# 04A-005.net
KiCad netlist of a schematic drawn in EAGLE
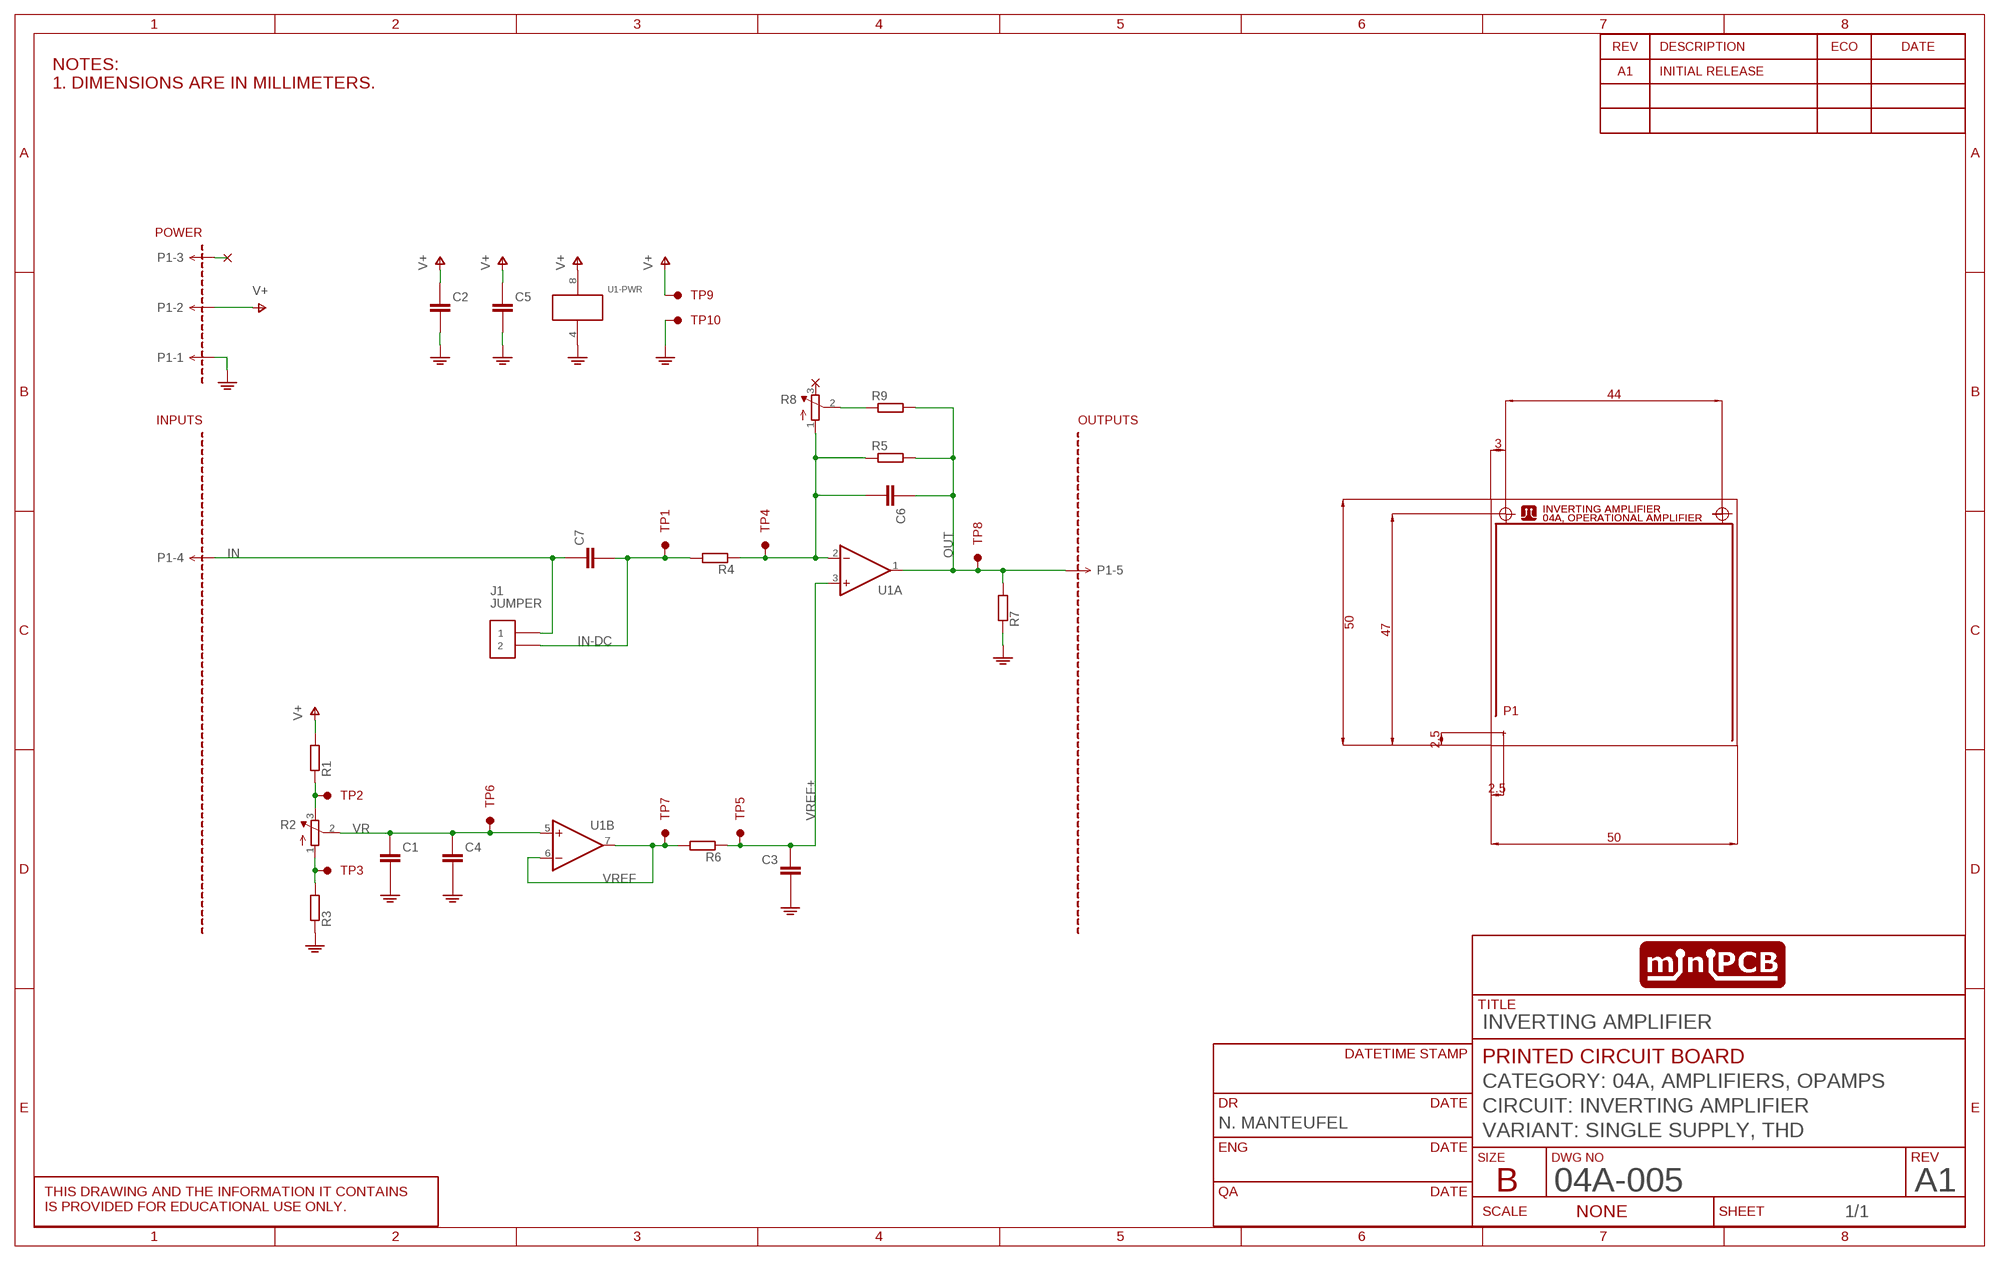
[diagram p0: schematic, sheet 1]

(export (version "E")
  (design (tool "Eeschema 10.0.6"))
  (components
    (comp (ref "C1")
      (value "CAPACITOR_10")
      (footprint "eagle-import:C5MM")
      (libsource (lib "eagle-import") (part "CAPACITOR_10"))
    )
    (comp (ref "C2")
      (value "CAPACITORTHD")
      (footprint "eagle-import:C050-024X044")
      (libsource (lib "eagle-import") (part "CAPACITORTHD"))
    )
    (comp (ref "C3")
      (value "CAPACITORTHD")
      (footprint "eagle-import:C050-024X044")
      (libsource (lib "eagle-import") (part "CAPACITORTHD"))
    )
    (comp (ref "C4")
      (value "CAPACITORTHD")
      (footprint "eagle-import:C050-024X044")
      (libsource (lib "eagle-import") (part "CAPACITORTHD"))
    )
    (comp (ref "C5")
      (value "CAPACITOR_10")
      (footprint "eagle-import:C5MM")
      (libsource (lib "eagle-import") (part "CAPACITOR_10"))
    )
    (comp (ref "C6")
      (value "CAPACITORTHD")
      (footprint "eagle-import:C050-024X044")
      (libsource (lib "eagle-import") (part "CAPACITORTHD"))
    )
    (comp (ref "C7")
      (value "CAPACITORTHD")
      (footprint "eagle-import:C050-024X044")
      (libsource (lib "eagle-import") (part "CAPACITORTHD"))
    )
    (comp (ref "J1")
      (value "JUMPER")
      (footprint "eagle-import:PINS_2")
      (libsource (lib "eagle-import") (part "PINS_2"))
    )
    (comp (ref "P1")
      (value "MINIPCB_5P5P")
      (footprint "eagle-import:PINS_1X5")
      (libsource (lib "eagle-import") (part "MINIPCB_5P5P"))
    )
    (comp (ref "R1")
      (value "RESISTOR10MM")
      (footprint "eagle-import:0207_10")
      (libsource (lib "eagle-import") (part "RESISTOR10MM"))
    )
    (comp (ref "R2")
      (value "TRIMPOT0.100THD")
      (footprint "eagle-import:TRIM_0100")
      (libsource (lib "eagle-import") (part "TRIMPOT0.100THD"))
    )
    (comp (ref "R3")
      (value "RESISTOR10MM")
      (footprint "eagle-import:0207_10")
      (libsource (lib "eagle-import") (part "RESISTOR10MM"))
    )
    (comp (ref "R4")
      (value "RESISTOR10MM")
      (footprint "eagle-import:0207_10")
      (libsource (lib "eagle-import") (part "RESISTOR10MM"))
    )
    (comp (ref "R5")
      (value "RESISTOR10MM")
      (footprint "eagle-import:0207_10")
      (libsource (lib "eagle-import") (part "RESISTOR10MM"))
    )
    (comp (ref "R6")
      (value "RESISTOR10MM")
      (footprint "eagle-import:0207_10")
      (libsource (lib "eagle-import") (part "RESISTOR10MM"))
    )
    (comp (ref "R7")
      (value "RESISTOR10MM")
      (footprint "eagle-import:0207_10")
      (libsource (lib "eagle-import") (part "RESISTOR10MM"))
    )
    (comp (ref "R8")
      (value "TRIMPOT0.100THD")
      (footprint "eagle-import:TRIM_0100")
      (libsource (lib "eagle-import") (part "TRIMPOT0.100THD"))
    )
    (comp (ref "R9")
      (value "RESISTOR10MM")
      (footprint "eagle-import:0207_10")
      (libsource (lib "eagle-import") (part "RESISTOR10MM"))
    )
    (comp (ref "TP1")
      (value "TESTPOINTKE5000-SMTEXT")
      (footprint "eagle-import:PINS_1_TESTPOINT_KE5000_NOTEXT")
      (libsource (lib "eagle-import") (part "TESTPOINTKE5000-SMTEXT"))
    )
    (comp (ref "TP2")
      (value "TESTPOINTKE5000-SMTEXT")
      (footprint "eagle-import:PINS_1_TESTPOINT_KE5000_NOTEXT")
      (libsource (lib "eagle-import") (part "TESTPOINTKE5000-SMTEXT"))
    )
    (comp (ref "TP3")
      (value "TESTPOINTKE5000-SMTEXT")
      (footprint "eagle-import:PINS_1_TESTPOINT_KE5000_NOTEXT")
      (libsource (lib "eagle-import") (part "TESTPOINTKE5000-SMTEXT"))
    )
    (comp (ref "TP4")
      (value "TESTPOINTKE5000-SMTEXT")
      (footprint "eagle-import:PINS_1_TESTPOINT_KE5000_NOTEXT")
      (libsource (lib "eagle-import") (part "TESTPOINTKE5000-SMTEXT"))
    )
    (comp (ref "TP5")
      (value "TESTPOINTKE5000-SMTEXT")
      (footprint "eagle-import:PINS_1_TESTPOINT_KE5000_NOTEXT")
      (libsource (lib "eagle-import") (part "TESTPOINTKE5000-SMTEXT"))
    )
    (comp (ref "TP6")
      (value "TESTPOINTKE5000-SMTEXT")
      (footprint "eagle-import:PINS_1_TESTPOINT_KE5000_NOTEXT")
      (libsource (lib "eagle-import") (part "TESTPOINTKE5000-SMTEXT"))
    )
    (comp (ref "TP7")
      (value "TESTPOINTKE5000-SMTEXT")
      (footprint "eagle-import:PINS_1_TESTPOINT_KE5000_NOTEXT")
      (libsource (lib "eagle-import") (part "TESTPOINTKE5000-SMTEXT"))
    )
    (comp (ref "TP8")
      (value "TESTPOINTKE5000-SMTEXT")
      (footprint "eagle-import:PINS_1_TESTPOINT_KE5000_NOTEXT")
      (libsource (lib "eagle-import") (part "TESTPOINTKE5000-SMTEXT"))
    )
    (comp (ref "TP9")
      (value "TESTPOINTKE5000-SMTEXT")
      (footprint "eagle-import:PINS_1_TESTPOINT_KE5000_NOTEXT")
      (libsource (lib "eagle-import") (part "TESTPOINTKE5000-SMTEXT"))
    )
    (comp (ref "TP10")
      (value "TESTPOINTKE5000-SMTEXT")
      (footprint "eagle-import:PINS_1_TESTPOINT_KE5000_NOTEXT")
      (libsource (lib "eagle-import") (part "TESTPOINTKE5000-SMTEXT"))
    )
    (comp (ref "U$1")
      (value "MINIPCB_50X50")
      (footprint "eagle-import:MINIPCB_0P_50X50MM")
      (fields
        (field (name "TITLE") "TITLE")
        (field (name "CIRCUIT_CATEGORY") "CIRCUIT CATEGORY")
        (field (name "PART_NUMBER") "PART NUMBER")
        (field (name "CIRCUIT_CATEGORY_1") "04A, OPERATIONAL AMPLIFIER")
        (field (name "PART_NUMBER_1") "04A-005")
        (field (name "REVISION") "A1-01")
        (field (name "TITLE_1") "INVERTING AMPLIFIER")
      )
      (libsource (lib "eagle-import") (part "MINIPCB_50X50"))
    )
    (comp (ref "U1")
      (value "OPAMP_DUALTHD")
      (footprint "eagle-import:DIL08")
      (libsource (lib "eagle-import") (part "OPAMP_DUALTHD"))
    )
  )
  (nets
    (net (code "1") (name "/IN") (class "Default")
      (node (ref "C7") (pin "1") (pinfunction "+_1") (pintype "passive"))
      (node (ref "J1") (pin "1") (pinfunction "1_1") (pintype "bidirectional"))
      (node (ref "P1") (pin "4") (pinfunction "1_4") (pintype "bidirectional"))
    )
    (net (code "2") (name "/IN-DC") (class "Default")
      (node (ref "C7") (pin "2") (pinfunction "-_2") (pintype "passive"))
      (node (ref "J1") (pin "2") (pinfunction "2_2") (pintype "bidirectional"))
      (node (ref "R4") (pin "2") (pinfunction "2_2") (pintype "passive"))
      (node (ref "TP1") (pin "1") (pinfunction "1_1") (pintype "bidirectional"))
    )
    (net (code "3") (name "/OUT") (class "Default")
      (node (ref "C6") (pin "1") (pinfunction "+_1") (pintype "passive"))
      (node (ref "P1") (pin "5") (pinfunction "1_5") (pintype "bidirectional"))
      (node (ref "R5") (pin "2") (pinfunction "2_2") (pintype "passive"))
      (node (ref "R7") (pin "2") (pinfunction "2_2") (pintype "passive"))
      (node (ref "R9") (pin "2") (pinfunction "2_2") (pintype "passive"))
      (node (ref "TP8") (pin "1") (pinfunction "1_1") (pintype "bidirectional"))
      (node (ref "U1") (pin "1") (pinfunction "OUT_1") (pintype "output"))
    )
    (net (code "4") (name "/VR") (class "Default")
      (node (ref "C1") (pin "+") (pinfunction "+_+") (pintype "passive"))
      (node (ref "C4") (pin "1") (pinfunction "+_1") (pintype "passive"))
      (node (ref "R2") (pin "2") (pinfunction "S_2") (pintype "passive"))
      (node (ref "TP6") (pin "1") (pinfunction "1_1") (pintype "bidirectional"))
      (node (ref "U1") (pin "5") (pinfunction "+IN_5") (pintype "input"))
    )
    (net (code "5") (name "/VREF") (class "Default")
      (node (ref "R6") (pin "2") (pinfunction "2_2") (pintype "passive"))
      (node (ref "TP7") (pin "1") (pinfunction "1_1") (pintype "bidirectional"))
      (node (ref "U1") (pin "6") (pinfunction "-IN_6") (pintype "input"))
      (node (ref "U1") (pin "7") (pinfunction "OUT_7") (pintype "output"))
    )
    (net (code "6") (name "/VREF+") (class "Default")
      (node (ref "C3") (pin "1") (pinfunction "+_1") (pintype "passive"))
      (node (ref "R6") (pin "1") (pinfunction "1_1") (pintype "passive"))
      (node (ref "TP5") (pin "1") (pinfunction "1_1") (pintype "bidirectional"))
      (node (ref "U1") (pin "3") (pinfunction "+IN_3") (pintype "input"))
    )
    (net (code "7") (name "GND") (class "Default")
      (node (ref "C1") (pin "-") (pinfunction "-_-") (pintype "passive"))
      (node (ref "C2") (pin "2") (pinfunction "-_2") (pintype "passive"))
      (node (ref "C3") (pin "2") (pinfunction "-_2") (pintype "passive"))
      (node (ref "C4") (pin "2") (pinfunction "-_2") (pintype "passive"))
      (node (ref "C5") (pin "-") (pinfunction "-_-") (pintype "passive"))
      (node (ref "P1") (pin "1") (pinfunction "1_1") (pintype "bidirectional"))
      (node (ref "R3") (pin "1") (pinfunction "1_1") (pintype "passive"))
      (node (ref "R7") (pin "1") (pinfunction "1_1") (pintype "passive"))
      (node (ref "TP10") (pin "1") (pinfunction "1_1") (pintype "bidirectional"))
      (node (ref "U1") (pin "4") (pinfunction "V-_4") (pintype "power_in"))
    )
    (net (code "8") (name "Net-(C6--)") (class "Default")
      (node (ref "C6") (pin "2") (pinfunction "-_2") (pintype "passive"))
      (node (ref "R4") (pin "1") (pinfunction "1_1") (pintype "passive"))
      (node (ref "R5") (pin "1") (pinfunction "1_1") (pintype "passive"))
      (node (ref "R8") (pin "1") (pinfunction "A_1") (pintype "passive"))
      (node (ref "TP4") (pin "1") (pinfunction "1_1") (pintype "bidirectional"))
      (node (ref "U1") (pin "2") (pinfunction "-IN_2") (pintype "input"))
    )
    (net (code "9") (name "Net-(R2-A)") (class "Default")
      (node (ref "R2") (pin "1") (pinfunction "A_1") (pintype "passive"))
      (node (ref "R3") (pin "2") (pinfunction "2_2") (pintype "passive"))
      (node (ref "TP3") (pin "1") (pinfunction "1_1") (pintype "bidirectional"))
    )
    (net (code "10") (name "Net-(R2-E)") (class "Default")
      (node (ref "R1") (pin "1") (pinfunction "1_1") (pintype "passive"))
      (node (ref "R2") (pin "3") (pinfunction "E_3") (pintype "passive"))
      (node (ref "TP2") (pin "1") (pinfunction "1_1") (pintype "bidirectional"))
    )
    (net (code "11") (name "Net-(R8-S)") (class "Default")
      (node (ref "R8") (pin "2") (pinfunction "S_2") (pintype "passive"))
      (node (ref "R9") (pin "1") (pinfunction "1_1") (pintype "passive"))
    )
    (net (code "12") (name "V+") (class "Default")
      (node (ref "C2") (pin "1") (pinfunction "+_1") (pintype "passive"))
      (node (ref "C5") (pin "+") (pinfunction "+_+") (pintype "passive"))
      (node (ref "P1") (pin "2") (pinfunction "1_2") (pintype "bidirectional"))
      (node (ref "R1") (pin "2") (pinfunction "2_2") (pintype "passive"))
      (node (ref "TP9") (pin "1") (pinfunction "1_1") (pintype "bidirectional"))
      (node (ref "U1") (pin "8") (pinfunction "V+_8") (pintype "power_in"))
    )
    (net (code "13") (name "unconnected-(P1C-1-Pad3)") (class "Default")
      (node (ref "P1") (pin "3") (pinfunction "1_3") (pintype "bidirectional"))
    )
    (net (code "14") (name "unconnected-(R8-E-Pad3)") (class "Default")
      (node (ref "R8") (pin "3") (pinfunction "E_3") (pintype "passive"))
    )
  )
)
